# Watch-It-TOP.net
KiCad netlist of a schematic drawn in EAGLE
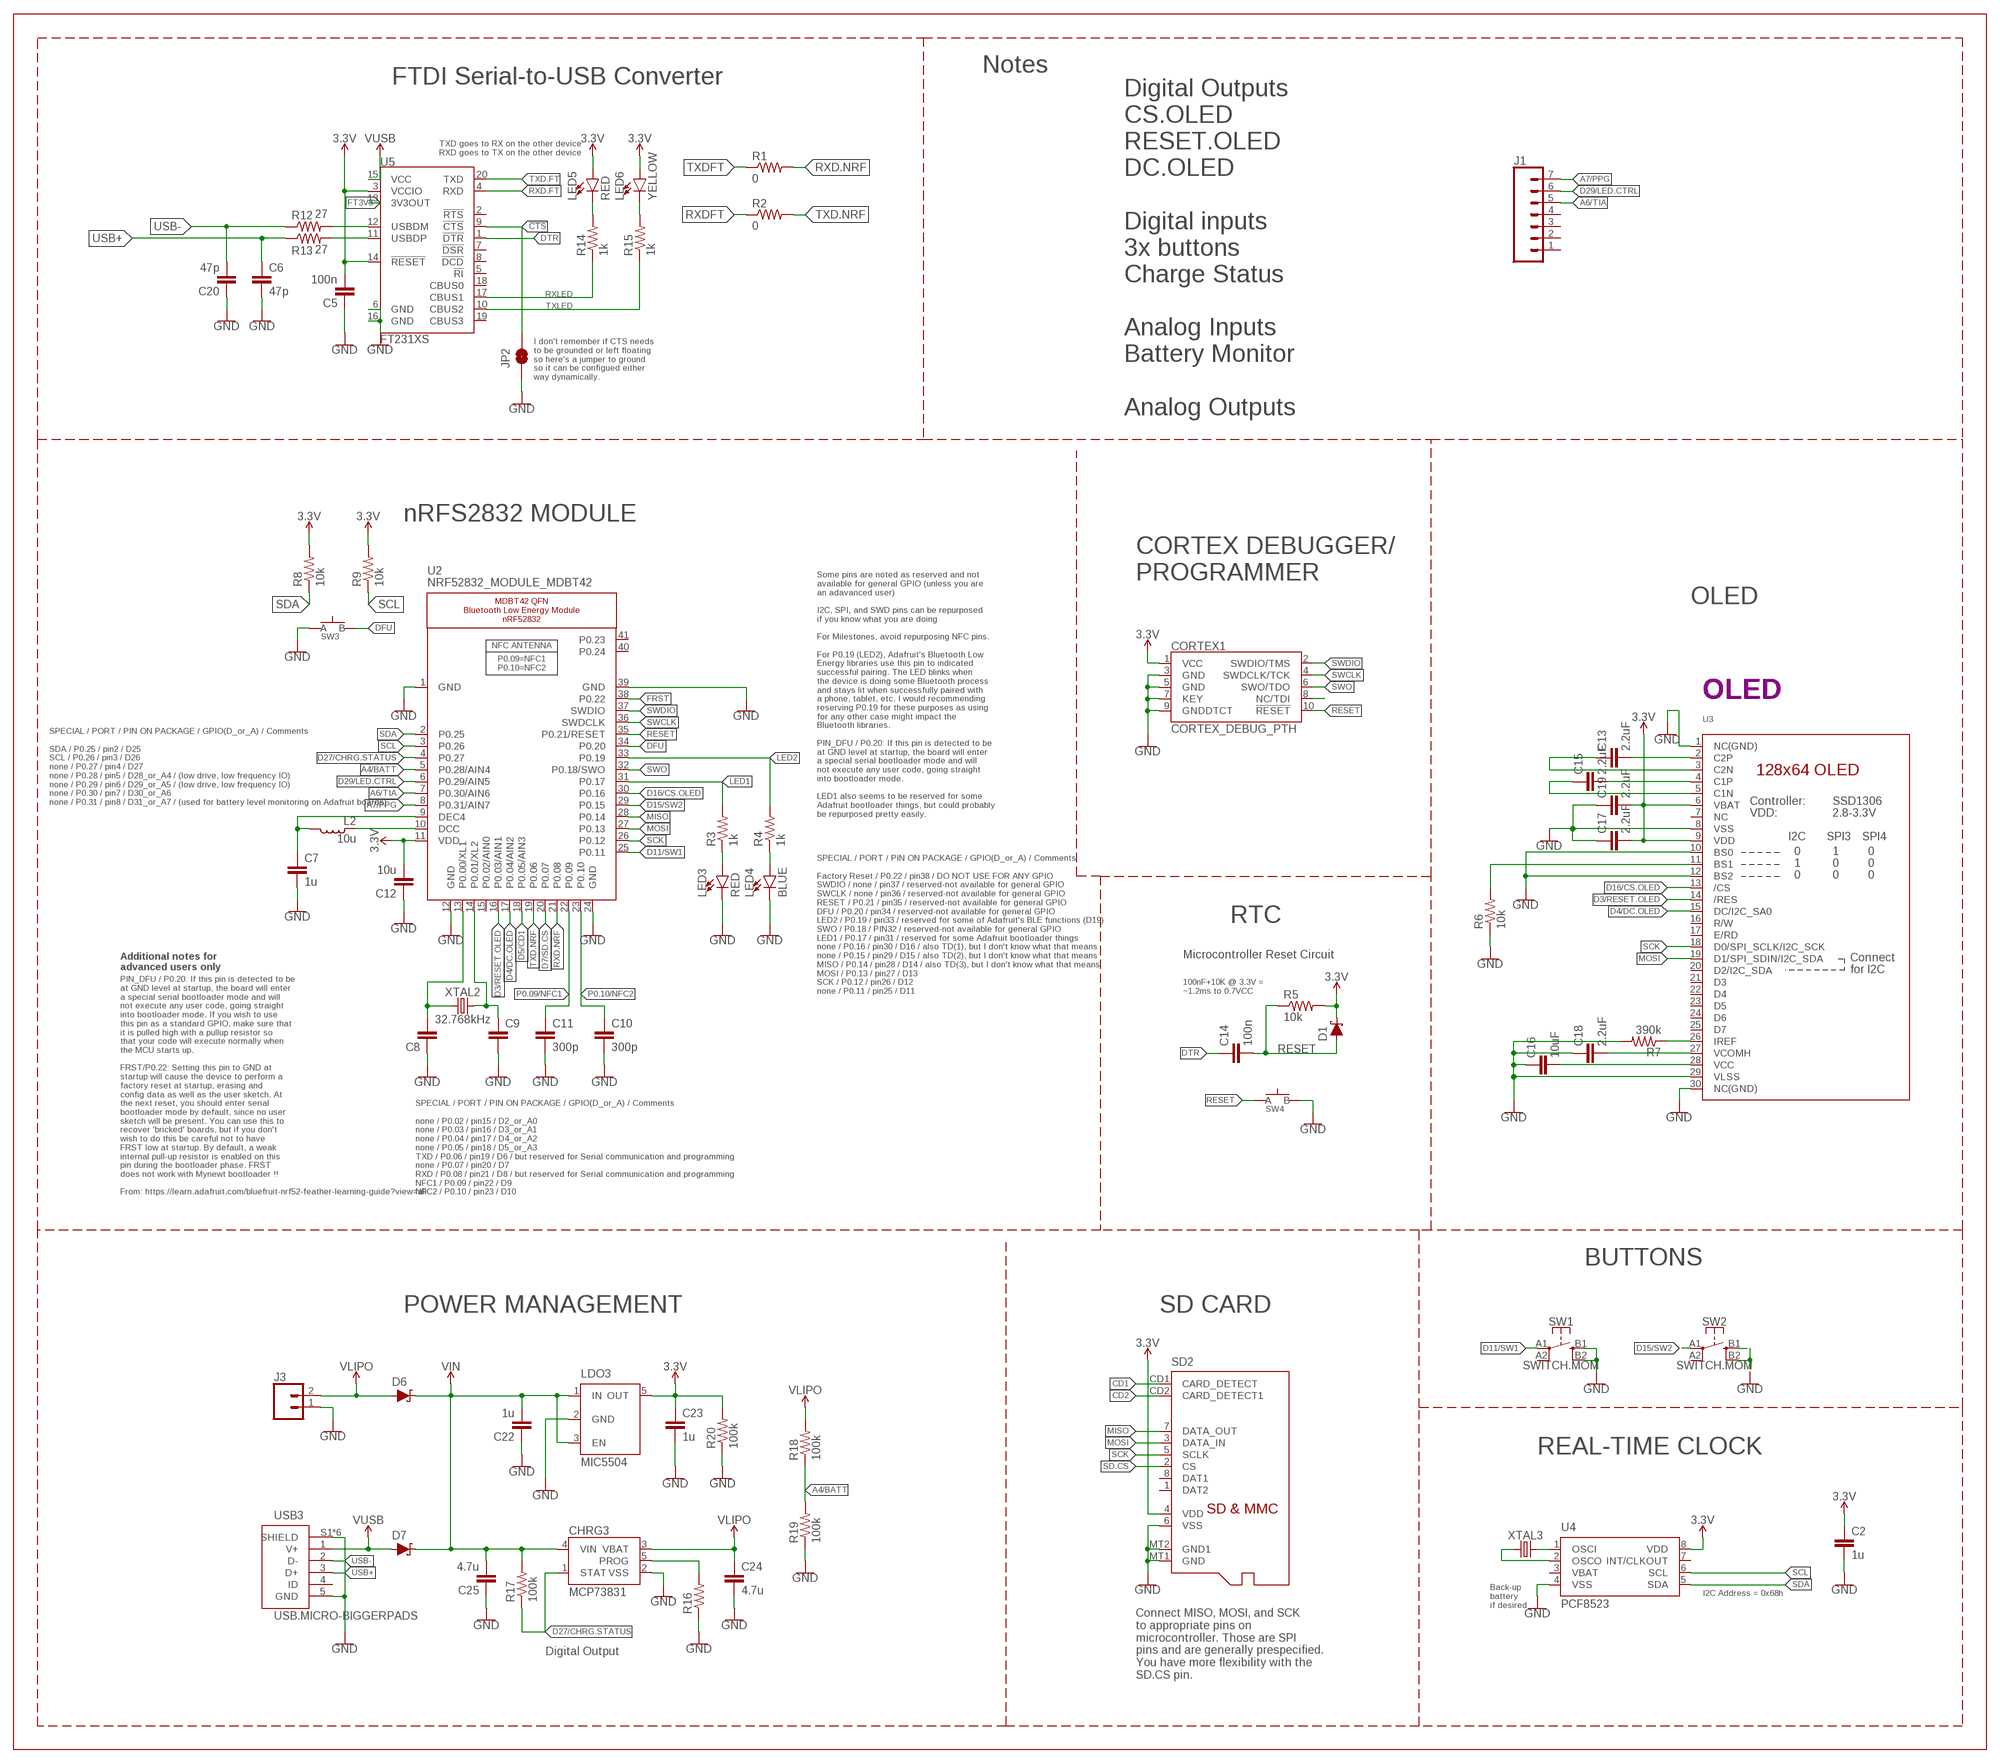
[diagram p0: schematic, sheet 1]

(export (version "E")
  (design (tool "Eeschema 10.0.6"))
  (components
    (comp (ref "C2")
      (value "1u")
      (footprint "eagle-import:C0603")
      (libsource (lib "eagle-import") (part "CAPACITOR0603"))
    )
    (comp (ref "C5")
      (value "100n")
      (footprint "eagle-import:C0603")
      (libsource (lib "eagle-import") (part "CAPACITOR0603"))
    )
    (comp (ref "C6")
      (value "47p")
      (footprint "eagle-import:C0603")
      (libsource (lib "eagle-import") (part "CAPACITOR0603"))
    )
    (comp (ref "C7")
      (value "1u")
      (footprint "eagle-import:C0603")
      (libsource (lib "eagle-import") (part "CAPACITOR0603"))
    )
    (comp (ref "C8")
      (value "CAPACITOR0603")
      (footprint "eagle-import:C0603")
      (libsource (lib "eagle-import") (part "CAPACITOR0603"))
    )
    (comp (ref "C9")
      (value "CAPACITOR0603")
      (footprint "eagle-import:C0603")
      (libsource (lib "eagle-import") (part "CAPACITOR0603"))
    )
    (comp (ref "C10")
      (value "300p")
      (footprint "eagle-import:C0603")
      (libsource (lib "eagle-import") (part "CAPACITOR0603"))
    )
    (comp (ref "C11")
      (value "300p")
      (footprint "eagle-import:C0603")
      (libsource (lib "eagle-import") (part "CAPACITOR0603"))
    )
    (comp (ref "C12")
      (value "10u")
      (footprint "eagle-import:C0805")
      (libsource (lib "eagle-import") (part "CAPACITOR0805"))
    )
    (comp (ref "C13")
      (value "2.2uF")
      (footprint "eagle-import:C0402")
      (libsource (lib "eagle-import") (part "CAPACITOR0402"))
    )
    (comp (ref "C14")
      (value "100n")
      (footprint "eagle-import:C0603")
      (libsource (lib "eagle-import") (part "CAPACITOR0603"))
    )
    (comp (ref "C15")
      (value "2.2uF")
      (footprint "eagle-import:C0402")
      (libsource (lib "eagle-import") (part "CAPACITOR0402"))
    )
    (comp (ref "C16")
      (value "10uF")
      (footprint "eagle-import:C0603")
      (libsource (lib "eagle-import") (part "CAPACITOR0603"))
    )
    (comp (ref "C17")
      (value "2.2uF")
      (footprint "eagle-import:C0402")
      (libsource (lib "eagle-import") (part "CAPACITOR0402"))
    )
    (comp (ref "C18")
      (value "2.2uF")
      (footprint "eagle-import:C0402")
      (libsource (lib "eagle-import") (part "CAPACITOR0402"))
    )
    (comp (ref "C19")
      (value "2.2uF")
      (footprint "eagle-import:C0402")
      (libsource (lib "eagle-import") (part "CAPACITOR0402"))
    )
    (comp (ref "C20")
      (value "47p")
      (footprint "eagle-import:C0603")
      (libsource (lib "eagle-import") (part "CAPACITOR0603"))
    )
    (comp (ref "C22")
      (value "1u")
      (footprint "eagle-import:C0603")
      (libsource (lib "eagle-import") (part "CAPACITOR0603"))
    )
    (comp (ref "C23")
      (value "1u")
      (footprint "eagle-import:C0603")
      (libsource (lib "eagle-import") (part "CAPACITOR0603"))
    )
    (comp (ref "C24")
      (value "4.7u")
      (footprint "eagle-import:C0603")
      (libsource (lib "eagle-import") (part "CAPACITOR0603"))
    )
    (comp (ref "C25")
      (value "4.7u")
      (footprint "eagle-import:C0603")
      (libsource (lib "eagle-import") (part "CAPACITOR0603"))
    )
    (comp (ref "CHRG3")
      (value "MCP73831")
      (footprint "eagle-import:SOT23-5")
      (libsource (lib "eagle-import") (part "MCP73831"))
    )
    (comp (ref "CORTEX1")
      (value "CORTEX_DEBUG_PTH")
      (footprint "eagle-import:2X5-PTH-1.27MM")
      (libsource (lib "eagle-import") (part "CORTEX_DEBUG_PTH"))
    )
    (comp (ref "D1")
      (value "SCHOTTKY-USC")
      (footprint "eagle-import:USC")
      (libsource (lib "eagle-import") (part "SCHOTTKY-USC"))
    )
    (comp (ref "D6")
      (value "SCHOTTKY-USC")
      (footprint "eagle-import:USC")
      (libsource (lib "eagle-import") (part "SCHOTTKY-USC"))
    )
    (comp (ref "D7")
      (value "SCHOTTKY-USC")
      (footprint "eagle-import:USC")
      (libsource (lib "eagle-import") (part "SCHOTTKY-USC"))
    )
    (comp (ref "J1")
      (value "CONN_07")
      (footprint "eagle-import:1X07")
      (libsource (lib "eagle-import") (part "CONN_07"))
    )
    (comp (ref "J3")
      (value "CONN_02")
      (footprint "eagle-import:1X02")
      (libsource (lib "eagle-import") (part "CONN_02"))
    )
    (comp (ref "JP2")
      (value "JUMPER-SMT_2_NO_SILK")
      (footprint "eagle-import:SMT-JUMPER_2_NO_SILK")
      (libsource (lib "eagle-import") (part "JUMPER-SMT_2_NO_SILK"))
    )
    (comp (ref "L2")
      (value "10u")
      (footprint "eagle-import:L0603")
      (libsource (lib "eagle-import") (part "INDUCTOR0603"))
    )
    (comp (ref "LDO3")
      (value "MIC5504")
      (footprint "eagle-import:SOT23-5")
      (libsource (lib "eagle-import") (part "MIC5504"))
    )
    (comp (ref "LED3")
      (value "RED")
      (footprint "eagle-import:LED-0603")
      (libsource (lib "eagle-import") (part "LED0603"))
    )
    (comp (ref "LED4")
      (value "BLUE")
      (footprint "eagle-import:LED-0603")
      (libsource (lib "eagle-import") (part "LED0603"))
    )
    (comp (ref "LED5")
      (value "RED")
      (footprint "eagle-import:LED-0603")
      (libsource (lib "eagle-import") (part "LED0603"))
    )
    (comp (ref "LED6")
      (value "YELLOW")
      (footprint "eagle-import:LED-0603")
      (libsource (lib "eagle-import") (part "LED0603"))
    )
    (comp (ref "R1")
      (value "0")
      (footprint "eagle-import:R0603")
      (libsource (lib "eagle-import") (part "RESISTOR0603"))
    )
    (comp (ref "R2")
      (value "0")
      (footprint "eagle-import:R0603")
      (libsource (lib "eagle-import") (part "RESISTOR0603"))
    )
    (comp (ref "R3")
      (value "1k")
      (footprint "eagle-import:R0603")
      (libsource (lib "eagle-import") (part "RESISTOR0603"))
    )
    (comp (ref "R4")
      (value "1k")
      (footprint "eagle-import:R0603")
      (libsource (lib "eagle-import") (part "RESISTOR0603"))
    )
    (comp (ref "R5")
      (value "10k")
      (footprint "eagle-import:R0603")
      (libsource (lib "eagle-import") (part "RESISTOR0603"))
    )
    (comp (ref "R6")
      (value "10k")
      (footprint "eagle-import:R0603")
      (libsource (lib "eagle-import") (part "RESISTOR0603"))
    )
    (comp (ref "R7")
      (value "390k")
      (footprint "eagle-import:R0603")
      (libsource (lib "eagle-import") (part "RESISTOR0603"))
    )
    (comp (ref "R8")
      (value "10k")
      (footprint "eagle-import:R0603")
      (libsource (lib "eagle-import") (part "RESISTOR0603"))
    )
    (comp (ref "R9")
      (value "10k")
      (footprint "eagle-import:R0603")
      (libsource (lib "eagle-import") (part "RESISTOR0603"))
    )
    (comp (ref "R12")
      (value "27")
      (footprint "eagle-import:R0603")
      (libsource (lib "eagle-import") (part "RESISTOR0603"))
    )
    (comp (ref "R13")
      (value "27")
      (footprint "eagle-import:R0603")
      (libsource (lib "eagle-import") (part "RESISTOR0603"))
    )
    (comp (ref "R14")
      (value "1k")
      (footprint "eagle-import:R0603")
      (libsource (lib "eagle-import") (part "RESISTOR0603"))
    )
    (comp (ref "R15")
      (value "1k")
      (footprint "eagle-import:R0603")
      (libsource (lib "eagle-import") (part "RESISTOR0603"))
    )
    (comp (ref "R16")
      (value "RESISTOR0603")
      (footprint "eagle-import:R0603")
      (libsource (lib "eagle-import") (part "RESISTOR0603"))
    )
    (comp (ref "R17")
      (value "100k")
      (footprint "eagle-import:R0603")
      (libsource (lib "eagle-import") (part "RESISTOR0603"))
    )
    (comp (ref "R18")
      (value "100k")
      (footprint "eagle-import:R0603")
      (libsource (lib "eagle-import") (part "RESISTOR0603"))
    )
    (comp (ref "R19")
      (value "100k")
      (footprint "eagle-import:R0603")
      (libsource (lib "eagle-import") (part "RESISTOR0603"))
    )
    (comp (ref "R20")
      (value "100k")
      (footprint "eagle-import:R0603")
      (libsource (lib "eagle-import") (part "RESISTOR0603"))
    )
    (comp (ref "SD2")
      (value "MICROSD")
      (footprint "eagle-import:MICROSD")
      (libsource (lib "eagle-import") (part "MICROSD"))
    )
    (comp (ref "SW1")
      (value "SWITCH.MOM")
      (footprint "eagle-import:TACTILE_SWITCH_SMD_6.2MM_TALL")
      (libsource (lib "eagle-import") (part "SWITCH.MOM"))
    )
    (comp (ref "SW2")
      (value "SWITCH.MOM")
      (footprint "eagle-import:TACTILE_SWITCH_SMD_6.2MM_TALL")
      (libsource (lib "eagle-import") (part "SWITCH.MOM"))
    )
    (comp (ref "SW3")
      (value "SPST-PTS830GG140-COPY.1-3")
      (footprint "eagle-import:BUTTON-GULLWING")
      (libsource (lib "eagle-import") (part "SPST-PTS830GG140-COPY.1-3"))
    )
    (comp (ref "SW4")
      (value "SPST-PTS830GG140-COPY.1-3")
      (footprint "eagle-import:BUTTON-GULLWING")
      (libsource (lib "eagle-import") (part "SPST-PTS830GG140-COPY.1-3"))
    )
    (comp (ref "U2")
      (value "NRF52832_MODULE_MDBT42")
      (footprint "eagle-import:BLE_MODULE_RAYTAC_MDBT42")
      (libsource (lib "eagle-import") (part "NRF52832_MODULE_MDBT42"))
    )
    (comp (ref "U3")
      (value "DISP_OLED_UG-2864HSWEG01-NO-WRAPAROUND")
      (footprint "eagle-import:UG-2864HSWEG01_0.96IN_NO-WRAPAROUND")
      (libsource (lib "eagle-import") (part "DISP_OLED_UG-2864HSWEG01-NO-WRAPAROUND"))
    )
    (comp (ref "U4")
      (value "PCF8523")
      (footprint "eagle-import:SO8")
      (libsource (lib "eagle-import") (part "PCF8523"))
    )
    (comp (ref "U5")
      (value "FT231XS")
      (footprint "eagle-import:SSOP20_L")
      (libsource (lib "eagle-import") (part "FT231XS"))
    )
    (comp (ref "USB3")
      (value "USB.MICRO-BIGGERPADS")
      (footprint "eagle-import:USB-MICRO-01.BIGGERPADS")
      (libsource (lib "eagle-import") (part "USB.MICRO-BIGGERPADS"))
    )
    (comp (ref "XTAL2")
      (value "32.768kHz")
      (footprint "eagle-import:2-SMD.NOLEAD.2.0MMTO1.2MM")
      (libsource (lib "eagle-import") (part "CRYSTALECS-.327-12.5-12-C-TR"))
    )
    (comp (ref "XTAL3")
      (value "32.7680kHz")
      (footprint "eagle-import:2-SMD.NOLEAD.2.0MMTO1.2MM")
      (fields (field (name "FREQ") "32.7680KHZ"))
      (libsource (lib "eagle-import") (part "CRYSTALECS-.327-12.5-12-C-TR"))
    )
  )
  (nets
    (net (code "1") (name "/RXLED") (class "Default")
      (node (ref "R14") (pin "1") (pinfunction "1_1") (pintype "passive"))
      (node (ref "U5") (pin "17") (pinfunction "CBUS1_17") (pintype "bidirectional"))
    )
    (net (code "2") (name "/TXLED") (class "Default")
      (node (ref "R15") (pin "1") (pinfunction "1_1") (pintype "passive"))
      (node (ref "U5") (pin "10") (pinfunction "CBUS2_10") (pintype "bidirectional"))
    )
    (net (code "3") (name "/VBAT") (class "Default")
      (node (ref "U4") (pin "3") (pinfunction "VBAT_3") (pintype "power_in"))
    )
    (net (code "4") (name "/~{CTS}") (class "Default")
      (node (ref "JP2") (pin "2") (pinfunction "2_2") (pintype "passive"))
      (node (ref "U5") (pin "9") (pinfunction "~{CTS}_9") (pintype "bidirectional"))
    )
    (net (code "5") (name "3.3V") (class "Default")
      (node (ref "C12") (pin "2") (pinfunction "2_2") (pintype "passive"))
      (node (ref "C17") (pin "2") (pinfunction "2_2") (pintype "passive"))
      (node (ref "C19") (pin "2") (pinfunction "2_2") (pintype "passive"))
      (node (ref "C2") (pin "1") (pinfunction "1_1") (pintype "passive"))
      (node (ref "C23") (pin "1") (pinfunction "1_1") (pintype "passive"))
      (node (ref "C5") (pin "2") (pinfunction "2_2") (pintype "passive"))
      (node (ref "CORTEX1") (pin "1") (pinfunction "VCC_1") (pintype "bidirectional"))
      (node (ref "D1") (pin "-") (pinfunction "C_-") (pintype "passive"))
      (node (ref "LDO3") (pin "5") (pinfunction "OUT_5") (pintype "bidirectional"))
      (node (ref "LED5") (pin "A") (pinfunction "A_A") (pintype "passive"))
      (node (ref "LED6") (pin "A") (pinfunction "A_A") (pintype "passive"))
      (node (ref "R20") (pin "2") (pinfunction "2_2") (pintype "passive"))
      (node (ref "R5") (pin "2") (pinfunction "2_2") (pintype "passive"))
      (node (ref "R8") (pin "2") (pinfunction "2_2") (pintype "passive"))
      (node (ref "R9") (pin "2") (pinfunction "2_2") (pintype "passive"))
      (node (ref "SD2") (pin "4") (pinfunction "VDD_4") (pintype "power_in"))
      (node (ref "U2") (pin "11") (pinfunction "VDD_11") (pintype "bidirectional"))
      (node (ref "U3") (pin "6") (pinfunction "VBAT_6") (pintype "input"))
      (node (ref "U3") (pin "9") (pinfunction "VDD_9") (pintype "power_in"))
      (node (ref "U4") (pin "8") (pinfunction "VDD_8") (pintype "power_in"))
      (node (ref "U5") (pin "14") (pinfunction "~{RESET}_14") (pintype "bidirectional"))
      (node (ref "U5") (pin "3") (pinfunction "VCCIO_3") (pintype "bidirectional"))
    )
    (net (code "6") (name "A4{slash}BATT") (class "Default")
      (node (ref "R18") (pin "1") (pinfunction "1_1") (pintype "passive"))
      (node (ref "R19") (pin "2") (pinfunction "2_2") (pintype "passive"))
      (node (ref "U2") (pin "5") (pinfunction "P0.28/AIN4_5") (pintype "bidirectional"))
    )
    (net (code "7") (name "A6{slash}TIA") (class "Default")
      (node (ref "J1") (pin "5") (pinfunction "5_5") (pintype "passive"))
      (node (ref "U2") (pin "7") (pinfunction "P0.30/AIN6_7") (pintype "bidirectional"))
    )
    (net (code "8") (name "A7{slash}PPG") (class "Default")
      (node (ref "J1") (pin "7") (pinfunction "7_7") (pintype "passive"))
      (node (ref "U2") (pin "8") (pinfunction "P0.31/AIN7_8") (pintype "bidirectional"))
    )
    (net (code "9") (name "CD1") (class "Default")
      (node (ref "SD2") (pin "CD1") (pinfunction "CARD_DETECT_CD1") (pintype "passive"))
    )
    (net (code "10") (name "CD2") (class "Default")
      (node (ref "SD2") (pin "CD2") (pinfunction "CARD_DETECT1_CD2") (pintype "passive"))
    )
    (net (code "11") (name "D3{slash}RESET.OLED") (class "Default")
      (node (ref "U2") (pin "16") (pinfunction "P0.03/AIN1_16") (pintype "bidirectional"))
      (node (ref "U3") (pin "14") (pinfunction "/RES_14") (pintype "input"))
    )
    (net (code "12") (name "D4{slash}DC.OLED") (class "Default")
      (node (ref "U2") (pin "17") (pinfunction "P0.04/AIN2_17") (pintype "bidirectional"))
      (node (ref "U3") (pin "15") (pinfunction "DC/I2C_SA0_15") (pintype "input"))
    )
    (net (code "13") (name "D5{slash}CD1") (class "Default")
      (node (ref "U2") (pin "18") (pinfunction "P0.05/AIN3_18") (pintype "bidirectional"))
    )
    (net (code "14") (name "D7{slash}SD.CS") (class "Default")
      (node (ref "U2") (pin "20") (pinfunction "P0.07_20") (pintype "bidirectional"))
    )
    (net (code "15") (name "D11{slash}SW1") (class "Default")
      (node (ref "SW1") (pin "A1") (pinfunction "1_A1") (pintype "passive"))
      (node (ref "U2") (pin "25") (pinfunction "P0.11_25") (pintype "bidirectional"))
    )
    (net (code "16") (name "D15{slash}SW2") (class "Default")
      (node (ref "SW2") (pin "A1") (pinfunction "1_A1") (pintype "passive"))
      (node (ref "U2") (pin "29") (pinfunction "P0.15_29") (pintype "bidirectional"))
    )
    (net (code "17") (name "D16{slash}CS.OLED") (class "Default")
      (node (ref "U2") (pin "30") (pinfunction "P0.16_30") (pintype "bidirectional"))
      (node (ref "U3") (pin "13") (pinfunction "/CS_13") (pintype "input"))
    )
    (net (code "18") (name "D27{slash}CHRG.STATUS") (class "Default")
      (node (ref "CHRG3") (pin "1") (pinfunction "STAT_1") (pintype "output"))
      (node (ref "R17") (pin "1") (pinfunction "1_1") (pintype "passive"))
      (node (ref "U2") (pin "4") (pinfunction "P0.27_4") (pintype "bidirectional"))
    )
    (net (code "19") (name "D29{slash}LED.CTRL") (class "Default")
      (node (ref "J1") (pin "6") (pinfunction "6_6") (pintype "passive"))
      (node (ref "U2") (pin "6") (pinfunction "P0.29/AIN5_6") (pintype "bidirectional"))
    )
    (net (code "20") (name "DFU") (class "Default")
      (node (ref "SW3") (pin "3") (pinfunction "B_3") (pintype "bidirectional"))
      (node (ref "U2") (pin "34") (pinfunction "P0.20_34") (pintype "bidirectional"))
    )
    (net (code "21") (name "DTR") (class "Default")
      (node (ref "C14") (pin "1") (pinfunction "1_1") (pintype "passive"))
      (node (ref "U5") (pin "1") (pinfunction "~{DTR}_1") (pintype "bidirectional"))
    )
    (net (code "22") (name "FRST") (class "Default")
      (node (ref "U2") (pin "38") (pinfunction "P0.22_38") (pintype "bidirectional"))
    )
    (net (code "23") (name "FT3V3") (class "Default")
      (node (ref "U5") (pin "13") (pinfunction "3V3OUT_13") (pintype "bidirectional"))
    )
    (net (code "24") (name "GND") (class "Default")
      (node (ref "C10") (pin "2") (pinfunction "2_2") (pintype "passive"))
      (node (ref "C11") (pin "2") (pinfunction "2_2") (pintype "passive"))
      (node (ref "C12") (pin "1") (pinfunction "1_1") (pintype "passive"))
      (node (ref "C16") (pin "1") (pinfunction "1_1") (pintype "passive"))
      (node (ref "C17") (pin "1") (pinfunction "1_1") (pintype "passive"))
      (node (ref "C18") (pin "1") (pinfunction "1_1") (pintype "passive"))
      (node (ref "C19") (pin "1") (pinfunction "1_1") (pintype "passive"))
      (node (ref "C2") (pin "2") (pinfunction "2_2") (pintype "passive"))
      (node (ref "C20") (pin "1") (pinfunction "1_1") (pintype "passive"))
      (node (ref "C22") (pin "1") (pinfunction "1_1") (pintype "passive"))
      (node (ref "C23") (pin "2") (pinfunction "2_2") (pintype "passive"))
      (node (ref "C24") (pin "2") (pinfunction "2_2") (pintype "passive"))
      (node (ref "C25") (pin "1") (pinfunction "1_1") (pintype "passive"))
      (node (ref "C5") (pin "1") (pinfunction "1_1") (pintype "passive"))
      (node (ref "C6") (pin "2") (pinfunction "2_2") (pintype "passive"))
      (node (ref "C7") (pin "2") (pinfunction "2_2") (pintype "passive"))
      (node (ref "C8") (pin "1") (pinfunction "1_1") (pintype "passive"))
      (node (ref "C9") (pin "2") (pinfunction "2_2") (pintype "passive"))
      (node (ref "CHRG3") (pin "2") (pinfunction "VSS_2") (pintype "power_in"))
      (node (ref "CORTEX1") (pin "3") (pinfunction "GND_3") (pintype "bidirectional"))
      (node (ref "CORTEX1") (pin "5") (pinfunction "GND_5") (pintype "bidirectional"))
      (node (ref "CORTEX1") (pin "7") (pinfunction "KEY_7") (pintype "bidirectional"))
      (node (ref "CORTEX1") (pin "9") (pinfunction "GNDDTCT_9") (pintype "bidirectional"))
      (node (ref "J3") (pin "1") (pinfunction "1_1") (pintype "passive"))
      (node (ref "JP2") (pin "1") (pinfunction "1_1") (pintype "passive"))
      (node (ref "LDO3") (pin "2") (pinfunction "GND_2") (pintype "bidirectional"))
      (node (ref "LED3") (pin "C") (pinfunction "C_C") (pintype "passive"))
      (node (ref "LED4") (pin "C") (pinfunction "C_C") (pintype "passive"))
      (node (ref "R16") (pin "1") (pinfunction "1_1") (pintype "passive"))
      (node (ref "R19") (pin "1") (pinfunction "1_1") (pintype "passive"))
      (node (ref "R20") (pin "1") (pinfunction "1_1") (pintype "passive"))
      (node (ref "R6") (pin "1") (pinfunction "1_1") (pintype "passive"))
      (node (ref "R7") (pin "2") (pinfunction "2_2") (pintype "passive"))
      (node (ref "SD2") (pin "6") (pinfunction "VSS_6") (pintype "power_in"))
      (node (ref "SD2") (pin "MT1") (pinfunction "GND_MT1") (pintype "power_in"))
      (node (ref "SD2") (pin "MT2") (pinfunction "GND1_MT2") (pintype "power_in"))
      (node (ref "SW1") (pin "B1") (pinfunction "3_B1") (pintype "passive"))
      (node (ref "SW1") (pin "B2") (pinfunction "4_B2") (pintype "passive"))
      (node (ref "SW2") (pin "B1") (pinfunction "3_B1") (pintype "passive"))
      (node (ref "SW2") (pin "B2") (pinfunction "4_B2") (pintype "passive"))
      (node (ref "SW3") (pin "1") (pinfunction "A_1") (pintype "bidirectional"))
      (node (ref "SW4") (pin "3") (pinfunction "B_3") (pintype "bidirectional"))
      (node (ref "U2") (pin "1") (pinfunction "GND_1") (pintype "bidirectional"))
      (node (ref "U2") (pin "12") (pinfunction "GND_12") (pintype "bidirectional"))
      (node (ref "U2") (pin "24") (pinfunction "GND_24") (pintype "bidirectional"))
      (node (ref "U2") (pin "39") (pinfunction "GND_39") (pintype "bidirectional"))
      (node (ref "U3") (pin "1") (pinfunction "NC(GND)_1") (pintype "input"))
      (node (ref "U3") (pin "10") (pinfunction "BS0_10") (pintype "input"))
      (node (ref "U3") (pin "12") (pinfunction "BS2_12") (pintype "input"))
      (node (ref "U3") (pin "29") (pinfunction "VLSS_29") (pintype "power_in"))
      (node (ref "U3") (pin "30") (pinfunction "NC(GND)_30") (pintype "input"))
      (node (ref "U3") (pin "8") (pinfunction "VSS_8") (pintype "power_in"))
      (node (ref "U4") (pin "4") (pinfunction "VSS_4") (pintype "power_in"))
      (node (ref "U5") (pin "16") (pinfunction "GND_16") (pintype "bidirectional"))
      (node (ref "U5") (pin "6") (pinfunction "GND_6") (pintype "bidirectional"))
      (node (ref "USB3") (pin "5") (pinfunction "GND_5") (pintype "bidirectional"))
      (node (ref "USB3") (pin "S1") (pinfunction "SHIELD_S1") (pintype "bidirectional"))
      (node (ref "USB3") (pin "S2") (pinfunction "SHIELD_S2") (pintype "bidirectional"))
      (node (ref "USB3") (pin "S3") (pinfunction "SHIELD_S3") (pintype "bidirectional"))
      (node (ref "USB3") (pin "S4") (pinfunction "SHIELD_S4") (pintype "bidirectional"))
      (node (ref "USB3") (pin "S5") (pinfunction "SHIELD_S5") (pintype "bidirectional"))
      (node (ref "USB3") (pin "S6") (pinfunction "SHIELD_S6") (pintype "bidirectional"))
    )
    (net (code "25") (name "LED1") (class "Default")
      (node (ref "R3") (pin "2") (pinfunction "2_2") (pintype "passive"))
      (node (ref "U2") (pin "31") (pinfunction "P0.17_31") (pintype "bidirectional"))
    )
    (net (code "26") (name "LED2") (class "Default")
      (node (ref "R4") (pin "2") (pinfunction "2_2") (pintype "passive"))
      (node (ref "U2") (pin "33") (pinfunction "P0.19_33") (pintype "bidirectional"))
    )
    (net (code "27") (name "MISO") (class "Default")
      (node (ref "SD2") (pin "7") (pinfunction "DATA_OUT_7") (pintype "output"))
      (node (ref "U2") (pin "28") (pinfunction "P0.14_28") (pintype "bidirectional"))
    )
    (net (code "28") (name "MOSI") (class "Default")
      (node (ref "SD2") (pin "3") (pinfunction "DATA_IN_3") (pintype "input"))
      (node (ref "U2") (pin "27") (pinfunction "P0.13_27") (pintype "bidirectional"))
      (node (ref "U3") (pin "19") (pinfunction "D1/SPI_SDIN/I2C_SDA_19") (pintype "bidirectional"))
    )
    (net (code "29") (name "Net-(CHRG3-PROG)") (class "Default")
      (node (ref "CHRG3") (pin "5") (pinfunction "PROG_5") (pintype "input"))
      (node (ref "R16") (pin "2") (pinfunction "2_2") (pintype "passive"))
    )
    (net (code "30") (name "Net-(LED3-PadA)") (class "Default")
      (node (ref "LED3") (pin "A") (pinfunction "A_A") (pintype "passive"))
      (node (ref "R3") (pin "1") (pinfunction "1_1") (pintype "passive"))
    )
    (net (code "31") (name "Net-(LED4-PadA)") (class "Default")
      (node (ref "LED4") (pin "A") (pinfunction "A_A") (pintype "passive"))
      (node (ref "R4") (pin "1") (pinfunction "1_1") (pintype "passive"))
    )
    (net (code "32") (name "Net-(LED5-PadC)") (class "Default")
      (node (ref "LED5") (pin "C") (pinfunction "C_C") (pintype "passive"))
      (node (ref "R14") (pin "2") (pinfunction "2_2") (pintype "passive"))
    )
    (net (code "33") (name "Net-(LED6-PadC)") (class "Default")
      (node (ref "LED6") (pin "C") (pinfunction "C_C") (pintype "passive"))
      (node (ref "R15") (pin "2") (pinfunction "2_2") (pintype "passive"))
    )
    (net (code "34") (name "Net-(U2-DCC)") (class "Default")
      (node (ref "L2") (pin "1") (pinfunction "1_1") (pintype "passive"))
      (node (ref "U2") (pin "10") (pinfunction "DCC_10") (pintype "bidirectional"))
    )
    (net (code "35") (name "Net-(U2-DEC4)") (class "Default")
      (node (ref "C7") (pin "1") (pinfunction "1_1") (pintype "passive"))
      (node (ref "L2") (pin "2") (pinfunction "2_2") (pintype "passive"))
      (node (ref "U2") (pin "9") (pinfunction "DEC4_9") (pintype "bidirectional"))
    )
    (net (code "36") (name "Net-(U2-P0.00{slash}XL1)") (class "Default")
      (node (ref "C8") (pin "2") (pinfunction "2_2") (pintype "passive"))
      (node (ref "U2") (pin "13") (pinfunction "P0.00/XL1_13") (pintype "bidirectional"))
      (node (ref "XTAL2") (pin "P$1") (pinfunction "1_P$1") (pintype "passive"))
    )
    (net (code "37") (name "Net-(U2-P0.01{slash}XL2)") (class "Default")
      (node (ref "C9") (pin "1") (pinfunction "1_1") (pintype "passive"))
      (node (ref "U2") (pin "14") (pinfunction "P0.01/XL2_14") (pintype "bidirectional"))
      (node (ref "XTAL2") (pin "P$2") (pinfunction "2_P$2") (pintype "passive"))
    )
    (net (code "38") (name "Net-(U3-BS1)") (class "Default")
      (node (ref "R6") (pin "2") (pinfunction "2_2") (pintype "passive"))
      (node (ref "U3") (pin "11") (pinfunction "BS1_11") (pintype "input"))
    )
    (net (code "39") (name "Net-(U3-C1N)") (class "Default")
      (node (ref "C15") (pin "1") (pinfunction "1_1") (pintype "passive"))
      (node (ref "U3") (pin "5") (pinfunction "C1N_5") (pintype "input"))
    )
    (net (code "40") (name "Net-(U3-C1P)") (class "Default")
      (node (ref "C15") (pin "2") (pinfunction "2_2") (pintype "passive"))
      (node (ref "U3") (pin "4") (pinfunction "C1P_4") (pintype "input"))
    )
    (net (code "41") (name "Net-(U3-C2N)") (class "Default")
      (node (ref "C13") (pin "1") (pinfunction "1_1") (pintype "passive"))
      (node (ref "U3") (pin "3") (pinfunction "C2N_3") (pintype "input"))
    )
    (net (code "42") (name "Net-(U3-C2P)") (class "Default")
      (node (ref "C13") (pin "2") (pinfunction "2_2") (pintype "passive"))
      (node (ref "U3") (pin "2") (pinfunction "C2P_2") (pintype "input"))
    )
    (net (code "43") (name "Net-(U3-IREF)") (class "Default")
      (node (ref "R7") (pin "1") (pinfunction "1_1") (pintype "passive"))
      (node (ref "U3") (pin "26") (pinfunction "IREF_26") (pintype "input"))
    )
    (net (code "44") (name "Net-(U3-VCC)") (class "Default")
      (node (ref "C16") (pin "2") (pinfunction "2_2") (pintype "passive"))
      (node (ref "U3") (pin "28") (pinfunction "VCC_28") (pintype "power_in"))
    )
    (net (code "45") (name "Net-(U3-VCOMH)") (class "Default")
      (node (ref "C18") (pin "2") (pinfunction "2_2") (pintype "passive"))
      (node (ref "U3") (pin "27") (pinfunction "VCOMH_27") (pintype "output"))
    )
    (net (code "46") (name "Net-(U4-OSCI)") (class "Default")
      (node (ref "U4") (pin "1") (pinfunction "OSCI_1") (pintype "bidirectional"))
      (node (ref "XTAL3") (pin "P$2") (pinfunction "2_P$2") (pintype "passive"))
    )
    (net (code "47") (name "Net-(U4-OSCO)") (class "Default")
      (node (ref "U4") (pin "2") (pinfunction "OSCO_2") (pintype "bidirectional"))
      (node (ref "XTAL3") (pin "P$1") (pinfunction "1_P$1") (pintype "passive"))
    )
    (net (code "48") (name "Net-(U5-USBDM)") (class "Default")
      (node (ref "R12") (pin "2") (pinfunction "2_2") (pintype "passive"))
      (node (ref "U5") (pin "12") (pinfunction "USBDM_12") (pintype "bidirectional"))
    )
    (net (code "49") (name "Net-(U5-USBDP)") (class "Default")
      (node (ref "R13") (pin "2") (pinfunction "2_2") (pintype "passive"))
      (node (ref "U5") (pin "11") (pinfunction "USBDP_11") (pintype "bidirectional"))
    )
    (net (code "50") (name "P0.09{slash}NFC1") (class "Default")
      (node (ref "C11") (pin "1") (pinfunction "1_1") (pintype "passive"))
      (node (ref "U2") (pin "22") (pinfunction "P0.09_22") (pintype "bidirectional"))
    )
    (net (code "51") (name "P0.10{slash}NFC2") (class "Default")
      (node (ref "C10") (pin "1") (pinfunction "1_1") (pintype "passive"))
      (node (ref "U2") (pin "23") (pinfunction "P0.10_23") (pintype "bidirectional"))
    )
    (net (code "52") (name "RESET") (class "Default")
      (node (ref "C14") (pin "2") (pinfunction "2_2") (pintype "passive"))
      (node (ref "CORTEX1") (pin "10") (pinfunction "~{RESET}_10") (pintype "bidirectional"))
      (node (ref "D1") (pin "+") (pinfunction "A_+") (pintype "passive"))
      (node (ref "R5") (pin "1") (pinfunction "1_1") (pintype "passive"))
      (node (ref "SW4") (pin "1") (pinfunction "A_1") (pintype "bidirectional"))
      (node (ref "U2") (pin "35") (pinfunction "P0.21/RESET_35") (pintype "bidirectional"))
    )
    (net (code "53") (name "RXD.FT") (class "Default")
      (node (ref "U5") (pin "4") (pinfunction "RXD_4") (pintype "bidirectional"))
    )
    (net (code "54") (name "RXD.NRF") (class "Default")
      (node (ref "R1") (pin "2") (pinfunction "2_2") (pintype "passive"))
      (node (ref "U2") (pin "21") (pinfunction "P0.08_21") (pintype "bidirectional"))
    )
    (net (code "55") (name "RXDFT") (class "Default")
      (node (ref "R2") (pin "1") (pinfunction "1_1") (pintype "passive"))
    )
    (net (code "56") (name "SCK") (class "Default")
      (node (ref "SD2") (pin "5") (pinfunction "SCLK_5") (pintype "input"))
      (node (ref "U2") (pin "26") (pinfunction "P0.12_26") (pintype "bidirectional"))
      (node (ref "U3") (pin "18") (pinfunction "D0/SPI_SCLK/I2C_SCK_18") (pintype "bidirectional"))
    )
    (net (code "57") (name "SCL") (class "Default")
      (node (ref "R9") (pin "1") (pinfunction "1_1") (pintype "passive"))
      (node (ref "U2") (pin "3") (pinfunction "P0.26_3") (pintype "bidirectional"))
      (node (ref "U4") (pin "6") (pinfunction "SCL_6") (pintype "bidirectional"))
    )
    (net (code "58") (name "SD.CS") (class "Default")
      (node (ref "SD2") (pin "2") (pinfunction "CS_2") (pintype "input"))
    )
    (net (code "59") (name "SDA") (class "Default")
      (node (ref "R8") (pin "1") (pinfunction "1_1") (pintype "passive"))
      (node (ref "U2") (pin "2") (pinfunction "P0.25_2") (pintype "bidirectional"))
      (node (ref "U4") (pin "5") (pinfunction "SDA_5") (pintype "bidirectional"))
    )
    (net (code "60") (name "SWCLK") (class "Default")
      (node (ref "CORTEX1") (pin "4") (pinfunction "SWDCLK/TCK_4") (pintype "bidirectional"))
      (node (ref "U2") (pin "36") (pinfunction "SWDCLK_36") (pintype "bidirectional"))
    )
    (net (code "61") (name "SWDIO") (class "Default")
      (node (ref "CORTEX1") (pin "2") (pinfunction "SWDIO/TMS_2") (pintype "bidirectional"))
      (node (ref "U2") (pin "37") (pinfunction "SWDIO_37") (pintype "bidirectional"))
    )
    (net (code "62") (name "SWO") (class "Default")
      (node (ref "CORTEX1") (pin "6") (pinfunction "SWO/TDO_6") (pintype "bidirectional"))
      (node (ref "U2") (pin "32") (pinfunction "P0.18/SWO_32") (pintype "bidirectional"))
    )
    (net (code "63") (name "TXD.FT") (class "Default")
      (node (ref "U5") (pin "20") (pinfunction "TXD_20") (pintype "bidirectional"))
    )
    (net (code "64") (name "TXD.NRF") (class "Default")
      (node (ref "R2") (pin "2") (pinfunction "2_2") (pintype "passive"))
      (node (ref "U2") (pin "19") (pinfunction "P0.06_19") (pintype "bidirectional"))
    )
    (net (code "65") (name "TXDFT") (class "Default")
      (node (ref "R1") (pin "1") (pinfunction "1_1") (pintype "passive"))
    )
    (net (code "66") (name "USB+") (class "Default")
      (node (ref "C6") (pin "1") (pinfunction "1_1") (pintype "passive"))
      (node (ref "R13") (pin "1") (pinfunction "1_1") (pintype "passive"))
      (node (ref "USB3") (pin "3") (pinfunction "D+_3") (pintype "bidirectional"))
    )
    (net (code "67") (name "USB-") (class "Default")
      (node (ref "C20") (pin "2") (pinfunction "2_2") (pintype "passive"))
      (node (ref "R12") (pin "1") (pinfunction "1_1") (pintype "passive"))
      (node (ref "USB3") (pin "2") (pinfunction "D-_2") (pintype "bidirectional"))
    )
    (net (code "68") (name "VIN") (class "Default")
      (node (ref "C22") (pin "2") (pinfunction "2_2") (pintype "passive"))
      (node (ref "C25") (pin "2") (pinfunction "2_2") (pintype "passive"))
      (node (ref "CHRG3") (pin "4") (pinfunction "VIN_4") (pintype "power_in"))
      (node (ref "D6") (pin "-") (pinfunction "C_-") (pintype "passive"))
      (node (ref "D7") (pin "-") (pinfunction "C_-") (pintype "passive"))
      (node (ref "LDO3") (pin "1") (pinfunction "IN_1") (pintype "bidirectional"))
      (node (ref "LDO3") (pin "3") (pinfunction "EN_3") (pintype "bidirectional"))
      (node (ref "R17") (pin "2") (pinfunction "2_2") (pintype "passive"))
    )
    (net (code "69") (name "VLIPO") (class "Default")
      (node (ref "C24") (pin "1") (pinfunction "1_1") (pintype "passive"))
      (node (ref "CHRG3") (pin "3") (pinfunction "VBAT_3") (pintype "power_in"))
      (node (ref "D6") (pin "+") (pinfunction "A_+") (pintype "passive"))
      (node (ref "J3") (pin "2") (pinfunction "2_2") (pintype "passive"))
      (node (ref "R18") (pin "2") (pinfunction "2_2") (pintype "passive"))
    )
    (net (code "70") (name "VUSB") (class "Default")
      (node (ref "D7") (pin "+") (pinfunction "A_+") (pintype "passive"))
      (node (ref "U5") (pin "15") (pinfunction "VCC_15") (pintype "bidirectional"))
      (node (ref "USB3") (pin "1") (pinfunction "V+_1") (pintype "bidirectional"))
    )
    (net (code "71") (name "unconnected-(CORTEX1-NC{slash}TDI-Pad8)") (class "Default")
      (node (ref "CORTEX1") (pin "8") (pinfunction "NC/TDI_8") (pintype "bidirectional"))
    )
    (net (code "72") (name "unconnected-(J1-Pad1)") (class "Default")
      (node (ref "J1") (pin "1") (pinfunction "1_1") (pintype "passive"))
    )
    (net (code "73") (name "unconnected-(J1-Pad2)") (class "Default")
      (node (ref "J1") (pin "2") (pinfunction "2_2") (pintype "passive"))
    )
    (net (code "74") (name "unconnected-(J1-Pad3)") (class "Default")
      (node (ref "J1") (pin "3") (pinfunction "3_3") (pintype "passive"))
    )
    (net (code "75") (name "unconnected-(J1-Pad4)") (class "Default")
      (node (ref "J1") (pin "4") (pinfunction "4_4") (pintype "passive"))
    )
    (net (code "76") (name "unconnected-(SD2-DAT1-Pad8)") (class "Default")
      (node (ref "SD2") (pin "8") (pinfunction "DAT1_8") (pintype "bidirectional"))
    )
    (net (code "77") (name "unconnected-(SD2-DAT2-Pad1)") (class "Default")
      (node (ref "SD2") (pin "1") (pinfunction "DAT2_1") (pintype "bidirectional"))
    )
    (net (code "78") (name "unconnected-(SW1-2-PadA2)") (class "Default")
      (node (ref "SW1") (pin "A2") (pinfunction "2_A2") (pintype "passive"))
    )
    (net (code "79") (name "unconnected-(SW2-2-PadA2)") (class "Default")
      (node (ref "SW2") (pin "A2") (pinfunction "2_A2") (pintype "passive"))
    )
    (net (code "80") (name "unconnected-(U2-P0.02{slash}AIN0-Pad15)") (class "Default")
      (node (ref "U2") (pin "15") (pinfunction "P0.02/AIN0_15") (pintype "bidirectional"))
    )
    (net (code "81") (name "unconnected-(U2-P0.23-Pad41)") (class "Default")
      (node (ref "U2") (pin "41") (pinfunction "P0.23_41") (pintype "bidirectional"))
    )
    (net (code "82") (name "unconnected-(U2-P0.24-Pad40)") (class "Default")
      (node (ref "U2") (pin "40") (pinfunction "P0.24_40") (pintype "bidirectional"))
    )
    (net (code "83") (name "unconnected-(U3-D2{slash}I2C_SDA-Pad20)") (class "Default")
      (node (ref "U3") (pin "20") (pinfunction "D2/I2C_SDA_20") (pintype "bidirectional"))
    )
    (net (code "84") (name "unconnected-(U3-D3-Pad21)") (class "Default")
      (node (ref "U3") (pin "21") (pinfunction "D3_21") (pintype "bidirectional"))
    )
    (net (code "85") (name "unconnected-(U3-D4-Pad22)") (class "Default")
      (node (ref "U3") (pin "22") (pinfunction "D4_22") (pintype "bidirectional"))
    )
    (net (code "86") (name "unconnected-(U3-D5-Pad23)") (class "Default")
      (node (ref "U3") (pin "23") (pinfunction "D5_23") (pintype "bidirectional"))
    )
    (net (code "87") (name "unconnected-(U3-D6-Pad24)") (class "Default")
      (node (ref "U3") (pin "24") (pinfunction "D6_24") (pintype "bidirectional"))
    )
    (net (code "88") (name "unconnected-(U3-D7-Pad25)") (class "Default")
      (node (ref "U3") (pin "25") (pinfunction "D7_25") (pintype "bidirectional"))
    )
    (net (code "89") (name "unconnected-(U3-E{slash}RD-Pad17)") (class "Default")
      (node (ref "U3") (pin "17") (pinfunction "E/RD_17") (pintype "input"))
    )
    (net (code "90") (name "unconnected-(U3-NC-Pad7)") (class "Default")
      (node (ref "U3") (pin "7") (pinfunction "NC_7") (pintype "no_connect"))
    )
    (net (code "91") (name "unconnected-(U3-R{slash}W-Pad16)") (class "Default")
      (node (ref "U3") (pin "16") (pinfunction "R/W_16") (pintype "input"))
    )
    (net (code "92") (name "unconnected-(U4-INT{slash}CLKOUT-Pad7)") (class "Default")
      (node (ref "U4") (pin "7") (pinfunction "INT/CLKOUT_7") (pintype "bidirectional"))
    )
    (net (code "93") (name "unconnected-(U5-CBUS0-Pad18)") (class "Default")
      (node (ref "U5") (pin "18") (pinfunction "CBUS0_18") (pintype "bidirectional"))
    )
    (net (code "94") (name "unconnected-(U5-CBUS3-Pad19)") (class "Default")
      (node (ref "U5") (pin "19") (pinfunction "CBUS3_19") (pintype "bidirectional"))
    )
    (net (code "95") (name "unconnected-(U5-~{DCD}-Pad8)") (class "Default")
      (node (ref "U5") (pin "8") (pinfunction "~{DCD}_8") (pintype "bidirectional"))
    )
    (net (code "96") (name "unconnected-(U5-~{DSR}-Pad7)") (class "Default")
      (node (ref "U5") (pin "7") (pinfunction "~{DSR}_7") (pintype "bidirectional"))
    )
    (net (code "97") (name "unconnected-(U5-~{RI}-Pad5)") (class "Default")
      (node (ref "U5") (pin "5") (pinfunction "~{RI}_5") (pintype "bidirectional"))
    )
    (net (code "98") (name "unconnected-(U5-~{RTS}-Pad2)") (class "Default")
      (node (ref "U5") (pin "2") (pinfunction "~{RTS}_2") (pintype "bidirectional"))
    )
    (net (code "99") (name "unconnected-(USB3-ID-Pad4)") (class "Default")
      (node (ref "USB3") (pin "4") (pinfunction "ID_4") (pintype "bidirectional"))
    )
  )
)
